# Sheet3_CP2102.net
KiCad netlist of a schematic drawn in Altium Designer
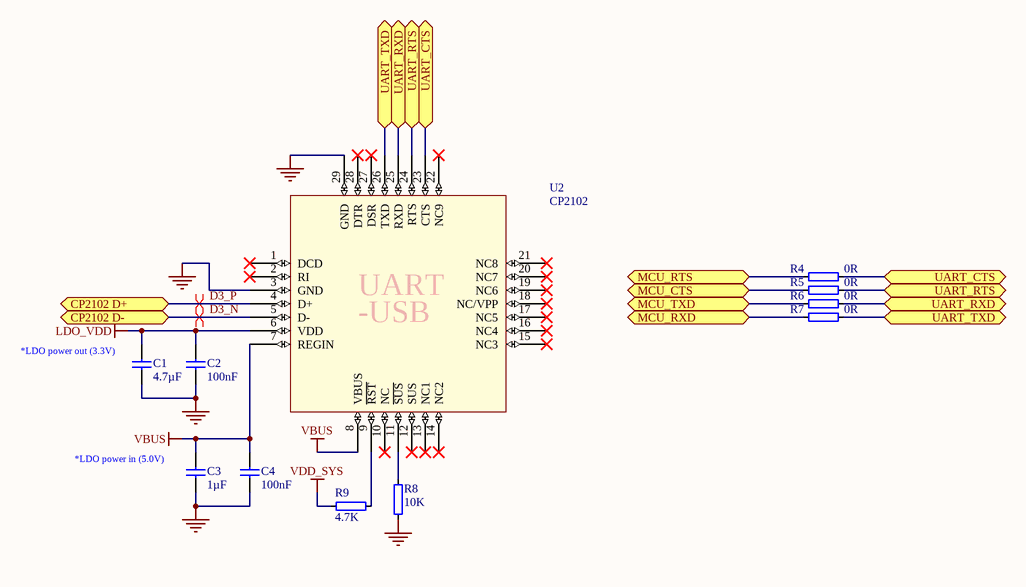
[diagram p0: Sheet3_CP2102.SchDoc]

(export (version "E")
  (design (tool "Eeschema 10.0.6"))
  (components
    (comp (ref "C1")
      (value "4.7µF")
      (footprint "0603_Imperial")
      (description "Genaral Schematic")
      (fields (field (name "TOLERANCE") "±5%"))
      (libsource (lib "Project_Library") (part "Capacitor"))
    )
    (comp (ref "C2")
      (value "100nF")
      (footprint "0402 imperial")
      (description "Genaral Schematic")
      (fields (field (name "TOLERANCE") "±5%"))
      (libsource (lib "Project_Library") (part "Capacitor"))
    )
    (comp (ref "C3")
      (value "1µF")
      (footprint "0603_Imperial")
      (description "Genaral Schematic")
      (fields (field (name "TOLERANCE") "±5%"))
      (libsource (lib "Project_Library") (part "Capacitor"))
    )
    (comp (ref "C4")
      (value "100nF")
      (footprint "0402 imperial")
      (description "Genaral Schematic")
      (fields (field (name "TOLERANCE") "±5%"))
      (libsource (lib "Project_Library") (part "Capacitor"))
    )
    (comp (ref "R4")
      (value "0R")
      (footprint "0402 imperial")
      (description "General Schematic")
      (fields (field (name "TOLERANCE") "±5%"))
      (libsource (lib "Project_Library") (part "Resistor"))
    )
    (comp (ref "R5")
      (value "0R")
      (footprint "0402 imperial")
      (description "General Schematic")
      (fields (field (name "TOLERANCE") "±5%"))
      (libsource (lib "Project_Library") (part "Resistor"))
    )
    (comp (ref "R6")
      (value "0R")
      (footprint "0402 imperial")
      (description "General Schematic")
      (fields (field (name "TOLERANCE") "±5%"))
      (libsource (lib "Project_Library") (part "Resistor"))
    )
    (comp (ref "R7")
      (value "0R")
      (footprint "0402 imperial")
      (description "General Schematic")
      (fields (field (name "TOLERANCE") "±5%"))
      (libsource (lib "Project_Library") (part "Resistor"))
    )
    (comp (ref "R8")
      (value "10K")
      (footprint "0402 imperial")
      (description "General Schematic")
      (fields (field (name "TOLERANCE") "±5%"))
      (libsource (lib "Project_Library") (part "Resistor"))
    )
    (comp (ref "R9")
      (value "4.7K")
      (footprint "0402 imperial")
      (description "General Schematic")
      (fields (field (name "TOLERANCE") "±5%"))
      (libsource (lib "Project_Library") (part "Resistor"))
    )
    (comp (ref "U2")
      (value "CP2102")
      (footprint "QFN28-CP2102")
      (description "Silicon Labs")
      (libsource (lib "Project_Library") (part "CP2102"))
    )
  )
  (nets
    (net (code "1") (name "/D3_N") (class "Default")
      (node (ref "U2") (pin "5") (pinfunction "D-_5") (pintype "bidirectional"))
    )
    (net (code "2") (name "/D3_P") (class "Default")
      (node (ref "U2") (pin "4") (pinfunction "D+_4") (pintype "bidirectional"))
    )
    (net (code "3") (name "/MCU_CTS") (class "Default")
      (node (ref "R5") (pin "1") (pinfunction "1_1") (pintype "passive"))
    )
    (net (code "4") (name "/MCU_RTS") (class "Default")
      (node (ref "R4") (pin "1") (pinfunction "1_1") (pintype "passive"))
    )
    (net (code "5") (name "/MCU_RXD") (class "Default")
      (node (ref "R7") (pin "1") (pinfunction "1_1") (pintype "passive"))
    )
    (net (code "6") (name "/MCU_TXD") (class "Default")
      (node (ref "R6") (pin "1") (pinfunction "1_1") (pintype "passive"))
    )
    (net (code "7") (name "/UART_CTS") (class "Default")
      (node (ref "R4") (pin "2") (pinfunction "2_2") (pintype "passive"))
      (node (ref "U2") (pin "23") (pinfunction "CTS_23") (pintype "bidirectional"))
    )
    (net (code "8") (name "/UART_RTS") (class "Default")
      (node (ref "R5") (pin "2") (pinfunction "2_2") (pintype "passive"))
      (node (ref "U2") (pin "24") (pinfunction "RTS_24") (pintype "bidirectional"))
    )
    (net (code "9") (name "/UART_RXD") (class "Default")
      (node (ref "R6") (pin "2") (pinfunction "2_2") (pintype "passive"))
      (node (ref "U2") (pin "25") (pinfunction "RXD_25") (pintype "bidirectional"))
    )
    (net (code "10") (name "/UART_TXD") (class "Default")
      (node (ref "R7") (pin "2") (pinfunction "2_2") (pintype "passive"))
      (node (ref "U2") (pin "26") (pinfunction "TXD_26") (pintype "bidirectional"))
    )
    (net (code "11") (name "GND") (class "Default")
      (node (ref "C1") (pin "1") (pinfunction "1_1") (pintype "passive"))
      (node (ref "C2") (pin "1") (pinfunction "1_1") (pintype "passive"))
      (node (ref "C3") (pin "1") (pinfunction "1_1") (pintype "passive"))
      (node (ref "C4") (pin "1") (pinfunction "1_1") (pintype "passive"))
      (node (ref "R8") (pin "2") (pinfunction "2_2") (pintype "passive"))
      (node (ref "U2") (pin "29") (pinfunction "GND_29") (pintype "bidirectional"))
      (node (ref "U2") (pin "3") (pinfunction "GND_3") (pintype "bidirectional"))
    )
    (net (code "12") (name "LDO_VDD") (class "Default")
      (node (ref "C1") (pin "2") (pinfunction "2_2") (pintype "passive"))
      (node (ref "C2") (pin "2") (pinfunction "2_2") (pintype "passive"))
      (node (ref "U2") (pin "6") (pinfunction "VDD_6") (pintype "bidirectional"))
    )
    (net (code "13") (name "Net-(U2-~{RST})") (class "Default")
      (node (ref "R9") (pin "1") (pinfunction "1_1") (pintype "passive"))
      (node (ref "U2") (pin "9") (pinfunction "~{RST}_9") (pintype "bidirectional"))
    )
    (net (code "14") (name "Net-(U2-~{SUS})") (class "Default")
      (node (ref "R8") (pin "1") (pinfunction "1_1") (pintype "passive"))
      (node (ref "U2") (pin "11") (pinfunction "~{SUS}_11") (pintype "bidirectional"))
    )
    (net (code "15") (name "VBUS") (class "Default")
      (node (ref "C3") (pin "2") (pinfunction "2_2") (pintype "passive"))
      (node (ref "C4") (pin "2") (pinfunction "2_2") (pintype "passive"))
      (node (ref "U2") (pin "7") (pinfunction "REGIN_7") (pintype "bidirectional"))
      (node (ref "U2") (pin "8") (pinfunction "VBUS_8") (pintype "bidirectional"))
    )
    (net (code "16") (name "VDD_SYS") (class "Default")
      (node (ref "R9") (pin "2") (pinfunction "2_2") (pintype "passive"))
    )
    (net (code "17") (name "unconnected-(U2-DCD-Pad1)") (class "Default")
      (node (ref "U2") (pin "1") (pinfunction "DCD_1") (pintype "bidirectional+no_connect"))
    )
    (net (code "18") (name "unconnected-(U2-DSR-Pad27)") (class "Default")
      (node (ref "U2") (pin "27") (pinfunction "DSR_27") (pintype "bidirectional+no_connect"))
    )
    (net (code "19") (name "unconnected-(U2-DTR-Pad28)") (class "Default")
      (node (ref "U2") (pin "28") (pinfunction "DTR_28") (pintype "bidirectional+no_connect"))
    )
    (net (code "20") (name "unconnected-(U2-NC-Pad10)") (class "Default")
      (node (ref "U2") (pin "10") (pinfunction "NC_10") (pintype "bidirectional+no_connect"))
    )
    (net (code "21") (name "unconnected-(U2-NC1-Pad13)") (class "Default")
      (node (ref "U2") (pin "13") (pinfunction "NC1_13") (pintype "bidirectional+no_connect"))
    )
    (net (code "22") (name "unconnected-(U2-NC2-Pad14)") (class "Default")
      (node (ref "U2") (pin "14") (pinfunction "NC2_14") (pintype "bidirectional+no_connect"))
    )
    (net (code "23") (name "unconnected-(U2-NC3-Pad15)") (class "Default")
      (node (ref "U2") (pin "15") (pinfunction "NC3_15") (pintype "bidirectional+no_connect"))
    )
    (net (code "24") (name "unconnected-(U2-NC4-Pad16)") (class "Default")
      (node (ref "U2") (pin "16") (pinfunction "NC4_16") (pintype "bidirectional+no_connect"))
    )
    (net (code "25") (name "unconnected-(U2-NC5-Pad17)") (class "Default")
      (node (ref "U2") (pin "17") (pinfunction "NC5_17") (pintype "bidirectional+no_connect"))
    )
    (net (code "26") (name "unconnected-(U2-NC6-Pad19)") (class "Default")
      (node (ref "U2") (pin "19") (pinfunction "NC6_19") (pintype "bidirectional+no_connect"))
    )
    (net (code "27") (name "unconnected-(U2-NC7-Pad20)") (class "Default")
      (node (ref "U2") (pin "20") (pinfunction "NC7_20") (pintype "bidirectional+no_connect"))
    )
    (net (code "28") (name "unconnected-(U2-NC8-Pad21)") (class "Default")
      (node (ref "U2") (pin "21") (pinfunction "NC8_21") (pintype "bidirectional+no_connect"))
    )
    (net (code "29") (name "unconnected-(U2-NC9-Pad22)") (class "Default")
      (node (ref "U2") (pin "22") (pinfunction "NC9_22") (pintype "bidirectional+no_connect"))
    )
    (net (code "30") (name "unconnected-(U2-NC{slash}VPP-Pad18)") (class "Default")
      (node (ref "U2") (pin "18") (pinfunction "NC/VPP_18") (pintype "bidirectional+no_connect"))
    )
    (net (code "31") (name "unconnected-(U2-RI-Pad2)") (class "Default")
      (node (ref "U2") (pin "2") (pinfunction "RI_2") (pintype "bidirectional+no_connect"))
    )
    (net (code "32") (name "unconnected-(U2-SUS-Pad12)") (class "Default")
      (node (ref "U2") (pin "12") (pinfunction "SUS_12") (pintype "bidirectional+no_connect"))
    )
  )
)
